# PowerManagement.net
KiCad netlist of a schematic drawn in Altium Designer
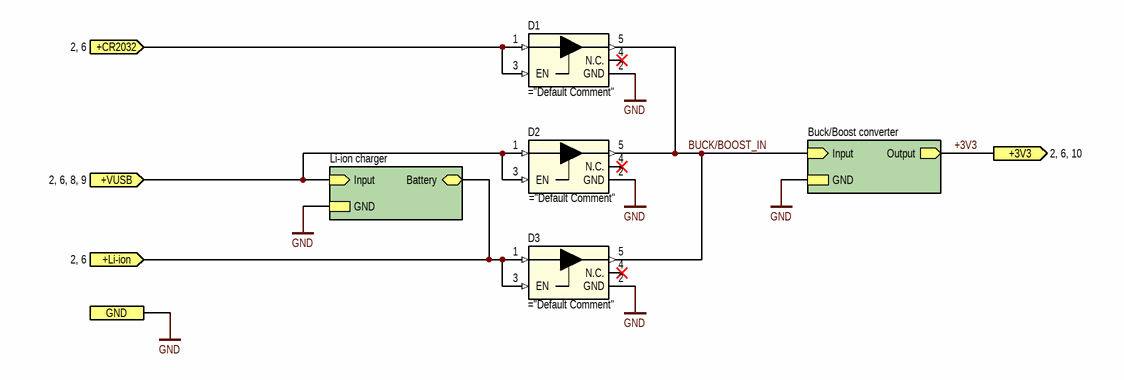
[diagram p0: PowerManagement.SchDoc]

(export (version "E")
  (design (tool "Eeschema 10.0.6"))
  (components
    (comp (ref "D1")
      (value "~")
      (description "IC IDEAL DIODE")
      (fields
        (field (name "TOLERANCE") "* %")
        (field (name "MANUFACTURER") "Analog Devices Inc./Maxim Integrated")
      )
      (libsource (lib "femtoino") (part "MAX40200"))
    )
    (comp (ref "D2")
      (value "~")
      (description "IC IDEAL DIODE")
      (fields
        (field (name "TOLERANCE") "* %")
        (field (name "MANUFACTURER") "Analog Devices Inc./Maxim Integrated")
      )
      (libsource (lib "femtoino") (part "MAX40200"))
    )
    (comp (ref "D3")
      (value "~")
      (description "IC IDEAL DIODE")
      (fields
        (field (name "TOLERANCE") "* %")
        (field (name "MANUFACTURER") "Analog Devices Inc./Maxim Integrated")
      )
      (libsource (lib "femtoino") (part "MAX40200"))
    )
  )
  (nets
    (net (code "2") (name "/+CR2032") (class "Default")
      (node (ref "D1") (pin "1") (pinfunction "VDD_1") (pintype "input"))
      (node (ref "D1") (pin "3") (pinfunction "EN_3") (pintype "input"))
    )
    (net (code "3") (name "/+Li-ion") (class "Default")
      (node (ref "D3") (pin "1") (pinfunction "VDD_1") (pintype "input"))
      (node (ref "D3") (pin "3") (pinfunction "EN_3") (pintype "input"))
    )
    (net (code "4") (name "/+VUSB") (class "Default")
      (node (ref "D2") (pin "1") (pinfunction "VDD_1") (pintype "input"))
      (node (ref "D2") (pin "3") (pinfunction "EN_3") (pintype "input"))
    )
    (net (code "5") (name "/BUCK{slash}BOOST_IN") (class "Default")
      (node (ref "D1") (pin "5") (pinfunction "OUT_5") (pintype "output"))
      (node (ref "D2") (pin "5") (pinfunction "OUT_5") (pintype "output"))
      (node (ref "D3") (pin "5") (pinfunction "OUT_5") (pintype "output"))
    )
    (net (code "6") (name "GND") (class "Default")
      (node (ref "D1") (pin "2") (pinfunction "GND_2") (pintype "passive"))
      (node (ref "D2") (pin "2") (pinfunction "GND_2") (pintype "passive"))
      (node (ref "D3") (pin "2") (pinfunction "GND_2") (pintype "passive"))
    )
    (net (code "7") (name "unconnected-(D1-N.C.-Pad4)") (class "Default")
      (node (ref "D1") (pin "4") (pinfunction "N.C._4") (pintype "passive+no_connect"))
    )
    (net (code "8") (name "unconnected-(D2-N.C.-Pad4)") (class "Default")
      (node (ref "D2") (pin "4") (pinfunction "N.C._4") (pintype "passive+no_connect"))
    )
    (net (code "9") (name "unconnected-(D3-N.C.-Pad4)") (class "Default")
      (node (ref "D3") (pin "4") (pinfunction "N.C._4") (pintype "passive+no_connect"))
    )
  )
)
